# projeto_-_Esquem_tico_v0_9.net
KiCad netlist of a schematic drawn in EAGLE
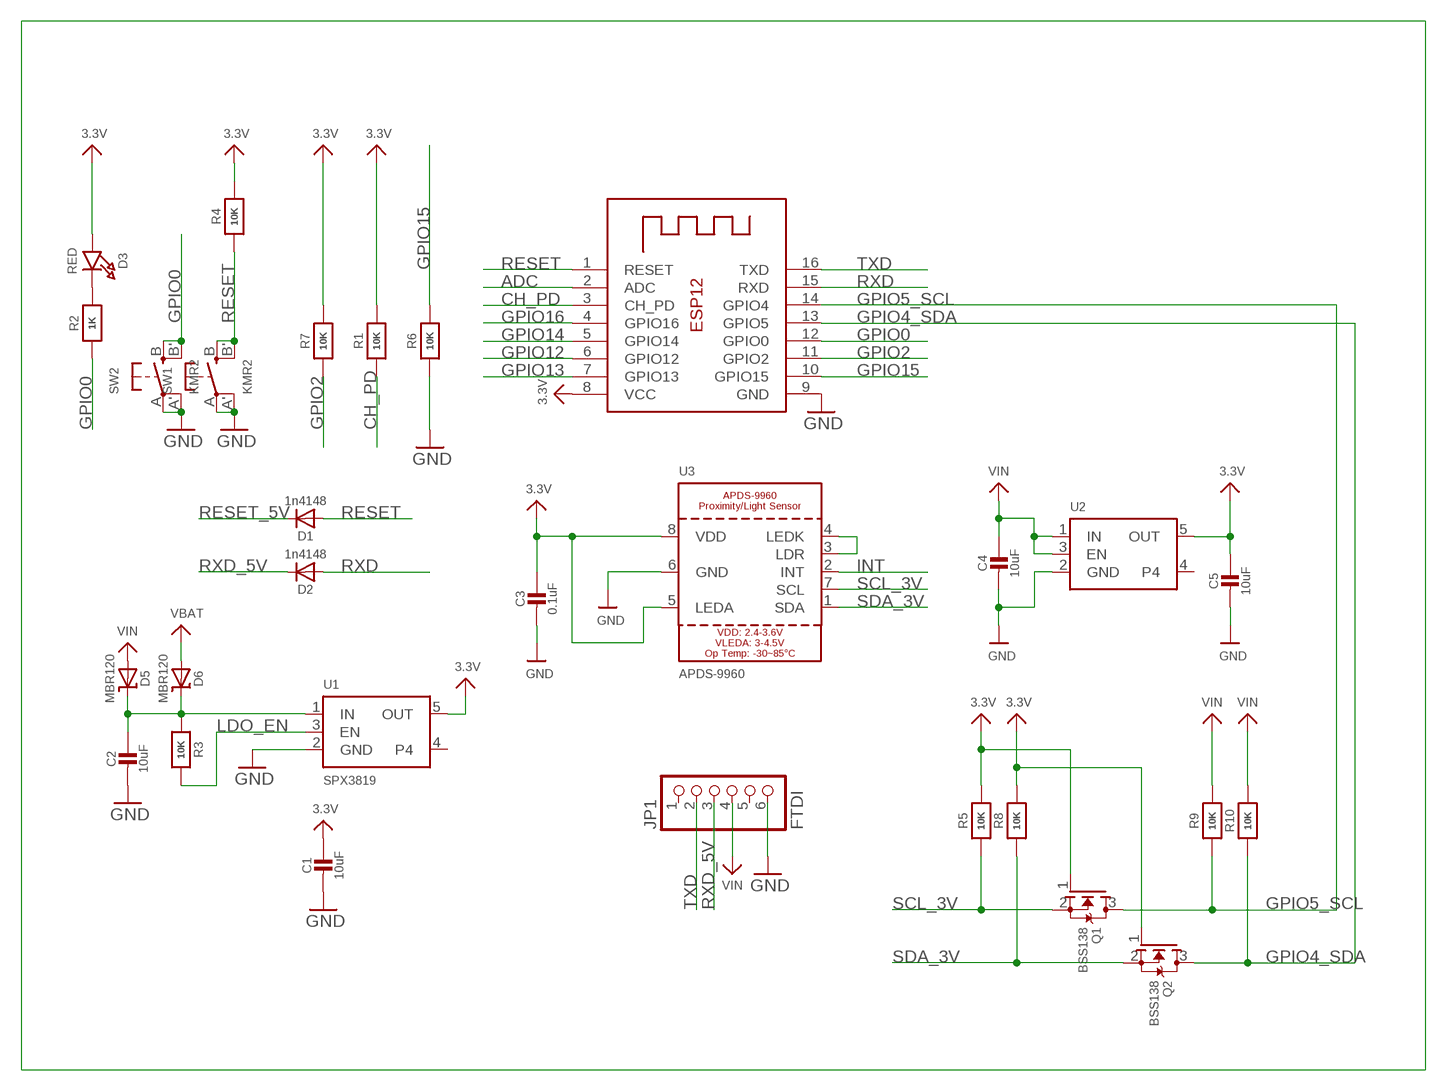
[diagram p0: schematic, sheet 1]

(export (version "E")
  (design (tool "Eeschema 10.0.6"))
  (components
    (comp (ref "C1")
      (value "10uF")
      (footprint "eagle-import:0805-NO")
      (libsource (lib "eagle-import") (part "CAP_CERAMIC0805-NOOUTLINE"))
    )
    (comp (ref "C2")
      (value "10uF")
      (footprint "eagle-import:0805-NO")
      (libsource (lib "eagle-import") (part "CAP_CERAMIC0805-NOOUTLINE"))
    )
    (comp (ref "C3")
      (value "0.1uF")
      (footprint "eagle-import:0805-NO")
      (libsource (lib "eagle-import") (part "CAP_CERAMIC0805-NOOUTLINE"))
    )
    (comp (ref "C4")
      (value "10uF")
      (footprint "eagle-import:0805-NO")
      (libsource (lib "eagle-import") (part "CAP_CERAMIC0805-NOOUTLINE"))
    )
    (comp (ref "C5")
      (value "10uF")
      (footprint "eagle-import:0805-NO")
      (libsource (lib "eagle-import") (part "CAP_CERAMIC0805-NOOUTLINE"))
    )
    (comp (ref "D1")
      (value "1n4148")
      (footprint "eagle-import:SOD-323")
      (libsource (lib "eagle-import") (part "DIODESOD-323"))
    )
    (comp (ref "D2")
      (value "1n4148")
      (footprint "eagle-import:SOD-323")
      (libsource (lib "eagle-import") (part "DIODESOD-323"))
    )
    (comp (ref "D3")
      (value "RED")
      (footprint "eagle-import:CHIPLED_0805_NOOUTLINE")
      (libsource (lib "eagle-import") (part "LED0805_NOOUTLINE"))
    )
    (comp (ref "D5")
      (value "MBR120")
      (footprint "eagle-import:SOD-123")
      (libsource (lib "eagle-import") (part "DIODE-SCHOTTKYSOD-123"))
    )
    (comp (ref "D6")
      (value "MBR120")
      (footprint "eagle-import:SOD-123")
      (libsource (lib "eagle-import") (part "DIODE-SCHOTTKYSOD-123"))
    )
    (comp (ref "JP1")
      (value "FTDI")
      (footprint "eagle-import:1X06_ROUND_70")
      (libsource (lib "eagle-import") (part "HEADER-1X670MIL"))
    )
    (comp (ref "Q1")
      (value "BSS138")
      (footprint "eagle-import:SOT23-WIDE")
      (libsource (lib "eagle-import") (part "MOSFET-NWIDE"))
    )
    (comp (ref "Q2")
      (value "BSS138")
      (footprint "eagle-import:SOT23-WIDE")
      (libsource (lib "eagle-import") (part "MOSFET-NWIDE"))
    )
    (comp (ref "R1")
      (value "10K")
      (footprint "eagle-import:0805-NO")
      (libsource (lib "eagle-import") (part "RESISTOR0805_NOOUTLINE"))
    )
    (comp (ref "R2")
      (value "1K")
      (footprint "eagle-import:0805-NO")
      (libsource (lib "eagle-import") (part "RESISTOR0805_NOOUTLINE"))
    )
    (comp (ref "R3")
      (value "10K")
      (footprint "eagle-import:0805-NO")
      (libsource (lib "eagle-import") (part "RESISTOR0805_NOOUTLINE"))
    )
    (comp (ref "R4")
      (value "10K")
      (footprint "eagle-import:0805-NO")
      (libsource (lib "eagle-import") (part "RESISTOR0805_NOOUTLINE"))
    )
    (comp (ref "R5")
      (value "10K")
      (footprint "eagle-import:0805-NO")
      (libsource (lib "eagle-import") (part "RESISTOR0805_NOOUTLINE"))
    )
    (comp (ref "R6")
      (value "10K")
      (footprint "eagle-import:0805-NO")
      (libsource (lib "eagle-import") (part "RESISTOR0805_NOOUTLINE"))
    )
    (comp (ref "R7")
      (value "10K")
      (footprint "eagle-import:0805-NO")
      (libsource (lib "eagle-import") (part "RESISTOR0805_NOOUTLINE"))
    )
    (comp (ref "R8")
      (value "10K")
      (footprint "eagle-import:0805-NO")
      (libsource (lib "eagle-import") (part "RESISTOR0805_NOOUTLINE"))
    )
    (comp (ref "R9")
      (value "10K")
      (footprint "eagle-import:0805-NO")
      (libsource (lib "eagle-import") (part "RESISTOR0805_NOOUTLINE"))
    )
    (comp (ref "R10")
      (value "10K")
      (footprint "eagle-import:0805-NO")
      (libsource (lib "eagle-import") (part "RESISTOR0805_NOOUTLINE"))
    )
    (comp (ref "SW1")
      (value "KMR2")
      (footprint "eagle-import:BTN_KMR2_4.6X2.8")
      (libsource (lib "eagle-import") (part "SWITCH_TACT_SMT4.6X2.8"))
    )
    (comp (ref "SW2")
      (value "KMR2")
      (footprint "eagle-import:BTN_KMR2_4.6X2.8")
      (libsource (lib "eagle-import") (part "SWITCH_TACT_SMT4.6X2.8"))
    )
    (comp (ref "U1")
      (value "SPX3819")
      (footprint "eagle-import:SOT23-5")
      (libsource (lib "eagle-import") (part "VREG_SOT23-5"))
    )
    (comp (ref "U2")
      (value "VREG_SOT23-5")
      (footprint "eagle-import:SOT23-5")
      (libsource (lib "eagle-import") (part "VREG_SOT23-5"))
    )
    (comp (ref "U3")
      (value "APDS-9960")
      (footprint "eagle-import:APDS-9960")
      (libsource (lib "eagle-import") (part "APDS-9960"))
    )
    (comp (ref "X1")
      (value "ESP-12")
      (footprint "eagle-import:ESP-12")
      (libsource (lib "eagle-import") (part "ESP-12"))
    )
  )
  (nets
    (net (code "1") (name "/ADC") (class "Default")
      (node (ref "X1") (pin "2") (pinfunction "ADC_2") (pintype "passive"))
    )
    (net (code "2") (name "/CH_PD") (class "Default")
      (node (ref "R1") (pin "1") (pinfunction "1_1") (pintype "passive"))
      (node (ref "X1") (pin "3") (pinfunction "CH_PD_3") (pintype "input"))
    )
    (net (code "3") (name "/GPIO0") (class "Default")
      (node (ref "R2") (pin "1") (pinfunction "1_1") (pintype "passive"))
      (node (ref "SW2") (pin "B") (pinfunction "S_B") (pintype "passive"))
      (node (ref "SW2") (pin "B'") (pinfunction "S1_B'") (pintype "passive"))
      (node (ref "X1") (pin "12") (pinfunction "GPIO0_12") (pintype "bidirectional"))
    )
    (net (code "4") (name "/GPIO2") (class "Default")
      (node (ref "R7") (pin "1") (pinfunction "1_1") (pintype "passive"))
      (node (ref "X1") (pin "11") (pinfunction "GPIO2_11") (pintype "bidirectional"))
    )
    (net (code "5") (name "/GPIO4_SDA") (class "Default")
      (node (ref "Q2") (pin "3") (pinfunction "D_3") (pintype "bidirectional"))
      (node (ref "R10") (pin "1") (pinfunction "1_1") (pintype "passive"))
      (node (ref "X1") (pin "13") (pinfunction "GPIO5_13") (pintype "bidirectional"))
    )
    (net (code "6") (name "/GPIO5_SCL") (class "Default")
      (node (ref "Q1") (pin "3") (pinfunction "D_3") (pintype "bidirectional"))
      (node (ref "R9") (pin "1") (pinfunction "1_1") (pintype "passive"))
      (node (ref "X1") (pin "14") (pinfunction "GPIO4_14") (pintype "bidirectional"))
    )
    (net (code "7") (name "/GPIO12") (class "Default")
      (node (ref "X1") (pin "6") (pinfunction "GPIO12_6") (pintype "bidirectional"))
    )
    (net (code "8") (name "/GPIO13") (class "Default")
      (node (ref "X1") (pin "7") (pinfunction "GPIO13_7") (pintype "bidirectional"))
    )
    (net (code "9") (name "/GPIO14") (class "Default")
      (node (ref "X1") (pin "5") (pinfunction "GPIO14_5") (pintype "bidirectional"))
    )
    (net (code "10") (name "/GPIO15") (class "Default")
      (node (ref "R6") (pin "2") (pinfunction "2_2") (pintype "passive"))
      (node (ref "X1") (pin "10") (pinfunction "GPIO15_10") (pintype "bidirectional"))
    )
    (net (code "11") (name "/GPIO16") (class "Default")
      (node (ref "X1") (pin "4") (pinfunction "GPIO16_4") (pintype "bidirectional"))
    )
    (net (code "12") (name "/INT") (class "Default")
      (node (ref "U3") (pin "2") (pinfunction "INT_2") (pintype "output"))
    )
    (net (code "13") (name "/LDO_EN") (class "Default")
      (node (ref "R3") (pin "2") (pinfunction "2_2") (pintype "passive"))
      (node (ref "U1") (pin "3") (pinfunction "EN_3") (pintype "input"))
    )
    (net (code "14") (name "/RESET") (class "Default")
      (node (ref "D1") (pin "A") (pinfunction "A_A") (pintype "passive"))
      (node (ref "R4") (pin "1") (pinfunction "1_1") (pintype "passive"))
      (node (ref "SW1") (pin "B") (pinfunction "S_B") (pintype "passive"))
      (node (ref "SW1") (pin "B'") (pinfunction "S1_B'") (pintype "passive"))
      (node (ref "X1") (pin "1") (pinfunction "RESET_1") (pintype "input"))
    )
    (net (code "15") (name "/RESET_5V") (class "Default")
      (node (ref "D1") (pin "C") (pinfunction "C_C") (pintype "passive"))
    )
    (net (code "16") (name "/RXD") (class "Default")
      (node (ref "D2") (pin "A") (pinfunction "A_A") (pintype "passive"))
      (node (ref "X1") (pin "15") (pinfunction "RXD_15") (pintype "input"))
    )
    (net (code "17") (name "/RXD_5V") (class "Default")
      (node (ref "D2") (pin "C") (pinfunction "C_C") (pintype "passive"))
      (node (ref "JP1") (pin "3") (pinfunction "3_3") (pintype "passive"))
    )
    (net (code "18") (name "/SCL_3V") (class "Default")
      (node (ref "Q1") (pin "2") (pinfunction "S_2") (pintype "bidirectional"))
      (node (ref "R5") (pin "1") (pinfunction "1_1") (pintype "passive"))
      (node (ref "U3") (pin "7") (pinfunction "SCL_7") (pintype "input"))
    )
    (net (code "19") (name "/SDA_3V") (class "Default")
      (node (ref "Q2") (pin "2") (pinfunction "S_2") (pintype "bidirectional"))
      (node (ref "R8") (pin "1") (pinfunction "1_1") (pintype "passive"))
      (node (ref "U3") (pin "1") (pinfunction "SDA_1") (pintype "bidirectional"))
    )
    (net (code "20") (name "/TXD") (class "Default")
      (node (ref "JP1") (pin "2") (pinfunction "2_2") (pintype "passive"))
      (node (ref "X1") (pin "16") (pinfunction "TXD_16") (pintype "output"))
    )
    (net (code "21") (name "3.3V") (class "Default")
      (node (ref "C1") (pin "1") (pinfunction "1_1") (pintype "passive"))
      (node (ref "C3") (pin "1") (pinfunction "1_1") (pintype "passive"))
      (node (ref "C5") (pin "1") (pinfunction "1_1") (pintype "passive"))
      (node (ref "D3") (pin "A") (pinfunction "A_A") (pintype "passive"))
      (node (ref "Q1") (pin "1") (pinfunction "G_1") (pintype "bidirectional"))
      (node (ref "Q2") (pin "1") (pinfunction "G_1") (pintype "bidirectional"))
      (node (ref "R1") (pin "2") (pinfunction "2_2") (pintype "passive"))
      (node (ref "R4") (pin "2") (pinfunction "2_2") (pintype "passive"))
      (node (ref "R5") (pin "2") (pinfunction "2_2") (pintype "passive"))
      (node (ref "R7") (pin "2") (pinfunction "2_2") (pintype "passive"))
      (node (ref "R8") (pin "2") (pinfunction "2_2") (pintype "passive"))
      (node (ref "U1") (pin "5") (pinfunction "OUT_5") (pintype "power_in"))
      (node (ref "U2") (pin "5") (pinfunction "OUT_5") (pintype "power_in"))
      (node (ref "U3") (pin "5") (pinfunction "LEDA_5") (pintype "power_in"))
      (node (ref "U3") (pin "8") (pinfunction "VDD_8") (pintype "power_in"))
      (node (ref "X1") (pin "8") (pinfunction "VCC_8") (pintype "power_in"))
    )
    (net (code "22") (name "GND") (class "Default")
      (node (ref "C1") (pin "2") (pinfunction "2_2") (pintype "passive"))
      (node (ref "C2") (pin "2") (pinfunction "2_2") (pintype "passive"))
      (node (ref "C3") (pin "2") (pinfunction "2_2") (pintype "passive"))
      (node (ref "C4") (pin "2") (pinfunction "2_2") (pintype "passive"))
      (node (ref "C5") (pin "2") (pinfunction "2_2") (pintype "passive"))
      (node (ref "JP1") (pin "6") (pinfunction "6_6") (pintype "passive"))
      (node (ref "R6") (pin "1") (pinfunction "1_1") (pintype "passive"))
      (node (ref "SW1") (pin "A") (pinfunction "P_A") (pintype "passive"))
      (node (ref "SW1") (pin "A'") (pinfunction "P1_A'") (pintype "passive"))
      (node (ref "SW2") (pin "A") (pinfunction "P_A") (pintype "passive"))
      (node (ref "SW2") (pin "A'") (pinfunction "P1_A'") (pintype "passive"))
      (node (ref "U1") (pin "2") (pinfunction "GND_2") (pintype "power_in"))
      (node (ref "U2") (pin "2") (pinfunction "GND_2") (pintype "power_in"))
      (node (ref "U3") (pin "6") (pinfunction "GND_6") (pintype "power_in"))
      (node (ref "X1") (pin "9") (pinfunction "GND_9") (pintype "power_in"))
    )
    (net (code "23") (name "Net-(D3-PadC)") (class "Default")
      (node (ref "D3") (pin "C") (pinfunction "C_C") (pintype "passive"))
      (node (ref "R2") (pin "2") (pinfunction "2_2") (pintype "passive"))
    )
    (net (code "24") (name "Net-(U1-IN)") (class "Default")
      (node (ref "C2") (pin "1") (pinfunction "1_1") (pintype "passive"))
      (node (ref "D5") (pin "C") (pinfunction "C_C") (pintype "passive"))
      (node (ref "D6") (pin "C") (pinfunction "C_C") (pintype "passive"))
      (node (ref "R3") (pin "1") (pinfunction "1_1") (pintype "passive"))
      (node (ref "U1") (pin "1") (pinfunction "IN_1") (pintype "power_in"))
    )
    (net (code "25") (name "Net-(U3-LDR)") (class "Default")
      (node (ref "U3") (pin "3") (pinfunction "LDR_3") (pintype "bidirectional"))
      (node (ref "U3") (pin "4") (pinfunction "LEDK_4") (pintype "bidirectional"))
    )
    (net (code "26") (name "VBAT") (class "Default")
      (node (ref "D6") (pin "A") (pinfunction "A_A") (pintype "passive"))
    )
    (net (code "27") (name "VIN") (class "Default")
      (node (ref "C4") (pin "1") (pinfunction "1_1") (pintype "passive"))
      (node (ref "D5") (pin "A") (pinfunction "A_A") (pintype "passive"))
      (node (ref "JP1") (pin "4") (pinfunction "4_4") (pintype "passive"))
      (node (ref "R10") (pin "2") (pinfunction "2_2") (pintype "passive"))
      (node (ref "R9") (pin "2") (pinfunction "2_2") (pintype "passive"))
      (node (ref "U2") (pin "1") (pinfunction "IN_1") (pintype "power_in"))
      (node (ref "U2") (pin "3") (pinfunction "EN_3") (pintype "input"))
    )
    (net (code "28") (name "unconnected-(JP1-Pad1)") (class "Default")
      (node (ref "JP1") (pin "1") (pinfunction "1_1") (pintype "passive"))
    )
    (net (code "29") (name "unconnected-(JP1-Pad5)") (class "Default")
      (node (ref "JP1") (pin "5") (pinfunction "5_5") (pintype "passive"))
    )
    (net (code "30") (name "unconnected-(U1-P4-Pad4)") (class "Default")
      (node (ref "U1") (pin "4") (pinfunction "P4_4") (pintype "bidirectional"))
    )
    (net (code "31") (name "unconnected-(U2-P4-Pad4)") (class "Default")
      (node (ref "U2") (pin "4") (pinfunction "P4_4") (pintype "bidirectional"))
    )
  )
)
